# Hall_Sensorv0_1.net
KiCad netlist of a schematic drawn in EAGLE
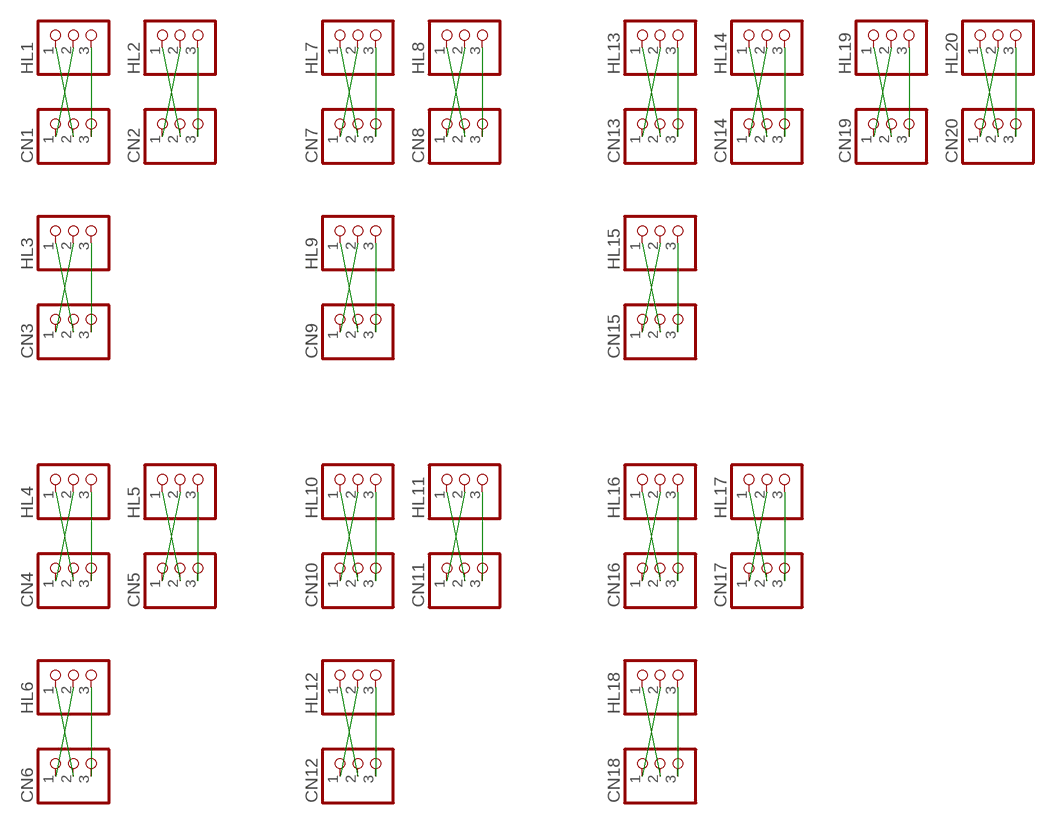
[diagram p0: schematic, sheet 1]

(export (version "E")
  (design (tool "Eeschema 10.0.6"))
  (components
    (comp (ref "CN1")
      (value "PINHD-1X3")
      (footprint "eagle-import:1X03")
      (libsource (lib "eagle-import") (part "PINHD-1X3"))
    )
    (comp (ref "CN2")
      (value "PINHD-1X3")
      (footprint "eagle-import:1X03")
      (libsource (lib "eagle-import") (part "PINHD-1X3"))
    )
    (comp (ref "CN3")
      (value "PINHD-1X3")
      (footprint "eagle-import:1X03")
      (libsource (lib "eagle-import") (part "PINHD-1X3"))
    )
    (comp (ref "CN4")
      (value "PINHD-1X3")
      (footprint "eagle-import:1X03")
      (libsource (lib "eagle-import") (part "PINHD-1X3"))
    )
    (comp (ref "CN5")
      (value "PINHD-1X3")
      (footprint "eagle-import:1X03")
      (libsource (lib "eagle-import") (part "PINHD-1X3"))
    )
    (comp (ref "CN6")
      (value "PINHD-1X3")
      (footprint "eagle-import:1X03")
      (libsource (lib "eagle-import") (part "PINHD-1X3"))
    )
    (comp (ref "CN7")
      (value "PINHD-1X3")
      (footprint "eagle-import:1X03")
      (libsource (lib "eagle-import") (part "PINHD-1X3"))
    )
    (comp (ref "CN8")
      (value "PINHD-1X3")
      (footprint "eagle-import:1X03")
      (libsource (lib "eagle-import") (part "PINHD-1X3"))
    )
    (comp (ref "CN9")
      (value "PINHD-1X3")
      (footprint "eagle-import:1X03")
      (libsource (lib "eagle-import") (part "PINHD-1X3"))
    )
    (comp (ref "CN10")
      (value "PINHD-1X3")
      (footprint "eagle-import:1X03")
      (libsource (lib "eagle-import") (part "PINHD-1X3"))
    )
    (comp (ref "CN11")
      (value "PINHD-1X3")
      (footprint "eagle-import:1X03")
      (libsource (lib "eagle-import") (part "PINHD-1X3"))
    )
    (comp (ref "CN12")
      (value "PINHD-1X3")
      (footprint "eagle-import:1X03")
      (libsource (lib "eagle-import") (part "PINHD-1X3"))
    )
    (comp (ref "CN13")
      (value "PINHD-1X3")
      (footprint "eagle-import:1X03")
      (libsource (lib "eagle-import") (part "PINHD-1X3"))
    )
    (comp (ref "CN14")
      (value "PINHD-1X3")
      (footprint "eagle-import:1X03")
      (libsource (lib "eagle-import") (part "PINHD-1X3"))
    )
    (comp (ref "CN15")
      (value "PINHD-1X3")
      (footprint "eagle-import:1X03")
      (libsource (lib "eagle-import") (part "PINHD-1X3"))
    )
    (comp (ref "CN16")
      (value "PINHD-1X3")
      (footprint "eagle-import:1X03")
      (libsource (lib "eagle-import") (part "PINHD-1X3"))
    )
    (comp (ref "CN17")
      (value "PINHD-1X3")
      (footprint "eagle-import:1X03")
      (libsource (lib "eagle-import") (part "PINHD-1X3"))
    )
    (comp (ref "CN18")
      (value "PINHD-1X3")
      (footprint "eagle-import:1X03")
      (libsource (lib "eagle-import") (part "PINHD-1X3"))
    )
    (comp (ref "CN19")
      (value "PINHD-1X3")
      (footprint "eagle-import:1X03")
      (libsource (lib "eagle-import") (part "PINHD-1X3"))
    )
    (comp (ref "CN20")
      (value "PINHD-1X3")
      (footprint "eagle-import:1X03")
      (libsource (lib "eagle-import") (part "PINHD-1X3"))
    )
    (comp (ref "HL1")
      (value "PINHD-1X3")
      (footprint "eagle-import:1X03")
      (libsource (lib "eagle-import") (part "PINHD-1X3"))
    )
    (comp (ref "HL2")
      (value "PINHD-1X3")
      (footprint "eagle-import:1X03")
      (libsource (lib "eagle-import") (part "PINHD-1X3"))
    )
    (comp (ref "HL3")
      (value "PINHD-1X3")
      (footprint "eagle-import:1X03")
      (libsource (lib "eagle-import") (part "PINHD-1X3"))
    )
    (comp (ref "HL4")
      (value "PINHD-1X3")
      (footprint "eagle-import:1X03")
      (libsource (lib "eagle-import") (part "PINHD-1X3"))
    )
    (comp (ref "HL5")
      (value "PINHD-1X3")
      (footprint "eagle-import:1X03")
      (libsource (lib "eagle-import") (part "PINHD-1X3"))
    )
    (comp (ref "HL6")
      (value "PINHD-1X3")
      (footprint "eagle-import:1X03")
      (libsource (lib "eagle-import") (part "PINHD-1X3"))
    )
    (comp (ref "HL7")
      (value "PINHD-1X3")
      (footprint "eagle-import:1X03")
      (libsource (lib "eagle-import") (part "PINHD-1X3"))
    )
    (comp (ref "HL8")
      (value "PINHD-1X3")
      (footprint "eagle-import:1X03")
      (libsource (lib "eagle-import") (part "PINHD-1X3"))
    )
    (comp (ref "HL9")
      (value "PINHD-1X3")
      (footprint "eagle-import:1X03")
      (libsource (lib "eagle-import") (part "PINHD-1X3"))
    )
    (comp (ref "HL10")
      (value "PINHD-1X3")
      (footprint "eagle-import:1X03")
      (libsource (lib "eagle-import") (part "PINHD-1X3"))
    )
    (comp (ref "HL11")
      (value "PINHD-1X3")
      (footprint "eagle-import:1X03")
      (libsource (lib "eagle-import") (part "PINHD-1X3"))
    )
    (comp (ref "HL12")
      (value "PINHD-1X3")
      (footprint "eagle-import:1X03")
      (libsource (lib "eagle-import") (part "PINHD-1X3"))
    )
    (comp (ref "HL13")
      (value "PINHD-1X3")
      (footprint "eagle-import:1X03")
      (libsource (lib "eagle-import") (part "PINHD-1X3"))
    )
    (comp (ref "HL14")
      (value "PINHD-1X3")
      (footprint "eagle-import:1X03")
      (libsource (lib "eagle-import") (part "PINHD-1X3"))
    )
    (comp (ref "HL15")
      (value "PINHD-1X3")
      (footprint "eagle-import:1X03")
      (libsource (lib "eagle-import") (part "PINHD-1X3"))
    )
    (comp (ref "HL16")
      (value "PINHD-1X3")
      (footprint "eagle-import:1X03")
      (libsource (lib "eagle-import") (part "PINHD-1X3"))
    )
    (comp (ref "HL17")
      (value "PINHD-1X3")
      (footprint "eagle-import:1X03")
      (libsource (lib "eagle-import") (part "PINHD-1X3"))
    )
    (comp (ref "HL18")
      (value "PINHD-1X3")
      (footprint "eagle-import:1X03")
      (libsource (lib "eagle-import") (part "PINHD-1X3"))
    )
    (comp (ref "HL19")
      (value "PINHD-1X3")
      (footprint "eagle-import:1X03")
      (libsource (lib "eagle-import") (part "PINHD-1X3"))
    )
    (comp (ref "HL20")
      (value "PINHD-1X3")
      (footprint "eagle-import:1X03")
      (libsource (lib "eagle-import") (part "PINHD-1X3"))
    )
  )
  (nets
    (net (code "1") (name "Net-(CN1-Pad1)") (class "Default")
      (node (ref "CN1") (pin "1") (pinfunction "1_1") (pintype "passive"))
      (node (ref "HL1") (pin "2") (pinfunction "2_2") (pintype "passive"))
    )
    (net (code "2") (name "Net-(CN1-Pad2)") (class "Default")
      (node (ref "CN1") (pin "2") (pinfunction "2_2") (pintype "passive"))
      (node (ref "HL1") (pin "1") (pinfunction "1_1") (pintype "passive"))
    )
    (net (code "3") (name "Net-(CN1-Pad3)") (class "Default")
      (node (ref "CN1") (pin "3") (pinfunction "3_3") (pintype "passive"))
      (node (ref "HL1") (pin "3") (pinfunction "3_3") (pintype "passive"))
    )
    (net (code "4") (name "Net-(CN2-Pad1)") (class "Default")
      (node (ref "CN2") (pin "1") (pinfunction "1_1") (pintype "passive"))
      (node (ref "HL2") (pin "2") (pinfunction "2_2") (pintype "passive"))
    )
    (net (code "5") (name "Net-(CN2-Pad2)") (class "Default")
      (node (ref "CN2") (pin "2") (pinfunction "2_2") (pintype "passive"))
      (node (ref "HL2") (pin "1") (pinfunction "1_1") (pintype "passive"))
    )
    (net (code "6") (name "Net-(CN2-Pad3)") (class "Default")
      (node (ref "CN2") (pin "3") (pinfunction "3_3") (pintype "passive"))
      (node (ref "HL2") (pin "3") (pinfunction "3_3") (pintype "passive"))
    )
    (net (code "7") (name "Net-(CN3-Pad1)") (class "Default")
      (node (ref "CN3") (pin "1") (pinfunction "1_1") (pintype "passive"))
      (node (ref "HL3") (pin "2") (pinfunction "2_2") (pintype "passive"))
    )
    (net (code "8") (name "Net-(CN3-Pad2)") (class "Default")
      (node (ref "CN3") (pin "2") (pinfunction "2_2") (pintype "passive"))
      (node (ref "HL3") (pin "1") (pinfunction "1_1") (pintype "passive"))
    )
    (net (code "9") (name "Net-(CN3-Pad3)") (class "Default")
      (node (ref "CN3") (pin "3") (pinfunction "3_3") (pintype "passive"))
      (node (ref "HL3") (pin "3") (pinfunction "3_3") (pintype "passive"))
    )
    (net (code "10") (name "Net-(CN4-Pad1)") (class "Default")
      (node (ref "CN4") (pin "1") (pinfunction "1_1") (pintype "passive"))
      (node (ref "HL4") (pin "2") (pinfunction "2_2") (pintype "passive"))
    )
    (net (code "11") (name "Net-(CN4-Pad2)") (class "Default")
      (node (ref "CN4") (pin "2") (pinfunction "2_2") (pintype "passive"))
      (node (ref "HL4") (pin "1") (pinfunction "1_1") (pintype "passive"))
    )
    (net (code "12") (name "Net-(CN4-Pad3)") (class "Default")
      (node (ref "CN4") (pin "3") (pinfunction "3_3") (pintype "passive"))
      (node (ref "HL4") (pin "3") (pinfunction "3_3") (pintype "passive"))
    )
    (net (code "13") (name "Net-(CN5-Pad1)") (class "Default")
      (node (ref "CN5") (pin "1") (pinfunction "1_1") (pintype "passive"))
      (node (ref "HL5") (pin "2") (pinfunction "2_2") (pintype "passive"))
    )
    (net (code "14") (name "Net-(CN5-Pad2)") (class "Default")
      (node (ref "CN5") (pin "2") (pinfunction "2_2") (pintype "passive"))
      (node (ref "HL5") (pin "1") (pinfunction "1_1") (pintype "passive"))
    )
    (net (code "15") (name "Net-(CN5-Pad3)") (class "Default")
      (node (ref "CN5") (pin "3") (pinfunction "3_3") (pintype "passive"))
      (node (ref "HL5") (pin "3") (pinfunction "3_3") (pintype "passive"))
    )
    (net (code "16") (name "Net-(CN6-Pad1)") (class "Default")
      (node (ref "CN6") (pin "1") (pinfunction "1_1") (pintype "passive"))
      (node (ref "HL6") (pin "2") (pinfunction "2_2") (pintype "passive"))
    )
    (net (code "17") (name "Net-(CN6-Pad2)") (class "Default")
      (node (ref "CN6") (pin "2") (pinfunction "2_2") (pintype "passive"))
      (node (ref "HL6") (pin "1") (pinfunction "1_1") (pintype "passive"))
    )
    (net (code "18") (name "Net-(CN6-Pad3)") (class "Default")
      (node (ref "CN6") (pin "3") (pinfunction "3_3") (pintype "passive"))
      (node (ref "HL6") (pin "3") (pinfunction "3_3") (pintype "passive"))
    )
    (net (code "19") (name "Net-(CN7-Pad1)") (class "Default")
      (node (ref "CN7") (pin "1") (pinfunction "1_1") (pintype "passive"))
      (node (ref "HL7") (pin "2") (pinfunction "2_2") (pintype "passive"))
    )
    (net (code "20") (name "Net-(CN7-Pad2)") (class "Default")
      (node (ref "CN7") (pin "2") (pinfunction "2_2") (pintype "passive"))
      (node (ref "HL7") (pin "1") (pinfunction "1_1") (pintype "passive"))
    )
    (net (code "21") (name "Net-(CN7-Pad3)") (class "Default")
      (node (ref "CN7") (pin "3") (pinfunction "3_3") (pintype "passive"))
      (node (ref "HL7") (pin "3") (pinfunction "3_3") (pintype "passive"))
    )
    (net (code "22") (name "Net-(CN8-Pad1)") (class "Default")
      (node (ref "CN8") (pin "1") (pinfunction "1_1") (pintype "passive"))
      (node (ref "HL8") (pin "2") (pinfunction "2_2") (pintype "passive"))
    )
    (net (code "23") (name "Net-(CN8-Pad2)") (class "Default")
      (node (ref "CN8") (pin "2") (pinfunction "2_2") (pintype "passive"))
      (node (ref "HL8") (pin "1") (pinfunction "1_1") (pintype "passive"))
    )
    (net (code "24") (name "Net-(CN8-Pad3)") (class "Default")
      (node (ref "CN8") (pin "3") (pinfunction "3_3") (pintype "passive"))
      (node (ref "HL8") (pin "3") (pinfunction "3_3") (pintype "passive"))
    )
    (net (code "25") (name "Net-(CN9-Pad1)") (class "Default")
      (node (ref "CN9") (pin "1") (pinfunction "1_1") (pintype "passive"))
      (node (ref "HL9") (pin "2") (pinfunction "2_2") (pintype "passive"))
    )
    (net (code "26") (name "Net-(CN9-Pad2)") (class "Default")
      (node (ref "CN9") (pin "2") (pinfunction "2_2") (pintype "passive"))
      (node (ref "HL9") (pin "1") (pinfunction "1_1") (pintype "passive"))
    )
    (net (code "27") (name "Net-(CN9-Pad3)") (class "Default")
      (node (ref "CN9") (pin "3") (pinfunction "3_3") (pintype "passive"))
      (node (ref "HL9") (pin "3") (pinfunction "3_3") (pintype "passive"))
    )
    (net (code "28") (name "Net-(CN10-Pad1)") (class "Default")
      (node (ref "CN10") (pin "1") (pinfunction "1_1") (pintype "passive"))
      (node (ref "HL10") (pin "2") (pinfunction "2_2") (pintype "passive"))
    )
    (net (code "29") (name "Net-(CN10-Pad2)") (class "Default")
      (node (ref "CN10") (pin "2") (pinfunction "2_2") (pintype "passive"))
      (node (ref "HL10") (pin "1") (pinfunction "1_1") (pintype "passive"))
    )
    (net (code "30") (name "Net-(CN10-Pad3)") (class "Default")
      (node (ref "CN10") (pin "3") (pinfunction "3_3") (pintype "passive"))
      (node (ref "HL10") (pin "3") (pinfunction "3_3") (pintype "passive"))
    )
    (net (code "31") (name "Net-(CN11-Pad1)") (class "Default")
      (node (ref "CN11") (pin "1") (pinfunction "1_1") (pintype "passive"))
      (node (ref "HL11") (pin "2") (pinfunction "2_2") (pintype "passive"))
    )
    (net (code "32") (name "Net-(CN11-Pad2)") (class "Default")
      (node (ref "CN11") (pin "2") (pinfunction "2_2") (pintype "passive"))
      (node (ref "HL11") (pin "1") (pinfunction "1_1") (pintype "passive"))
    )
    (net (code "33") (name "Net-(CN11-Pad3)") (class "Default")
      (node (ref "CN11") (pin "3") (pinfunction "3_3") (pintype "passive"))
      (node (ref "HL11") (pin "3") (pinfunction "3_3") (pintype "passive"))
    )
    (net (code "34") (name "Net-(CN12-Pad1)") (class "Default")
      (node (ref "CN12") (pin "1") (pinfunction "1_1") (pintype "passive"))
      (node (ref "HL12") (pin "2") (pinfunction "2_2") (pintype "passive"))
    )
    (net (code "35") (name "Net-(CN12-Pad2)") (class "Default")
      (node (ref "CN12") (pin "2") (pinfunction "2_2") (pintype "passive"))
      (node (ref "HL12") (pin "1") (pinfunction "1_1") (pintype "passive"))
    )
    (net (code "36") (name "Net-(CN12-Pad3)") (class "Default")
      (node (ref "CN12") (pin "3") (pinfunction "3_3") (pintype "passive"))
      (node (ref "HL12") (pin "3") (pinfunction "3_3") (pintype "passive"))
    )
    (net (code "37") (name "Net-(CN13-Pad1)") (class "Default")
      (node (ref "CN13") (pin "1") (pinfunction "1_1") (pintype "passive"))
      (node (ref "HL13") (pin "2") (pinfunction "2_2") (pintype "passive"))
    )
    (net (code "38") (name "Net-(CN13-Pad2)") (class "Default")
      (node (ref "CN13") (pin "2") (pinfunction "2_2") (pintype "passive"))
      (node (ref "HL13") (pin "1") (pinfunction "1_1") (pintype "passive"))
    )
    (net (code "39") (name "Net-(CN13-Pad3)") (class "Default")
      (node (ref "CN13") (pin "3") (pinfunction "3_3") (pintype "passive"))
      (node (ref "HL13") (pin "3") (pinfunction "3_3") (pintype "passive"))
    )
    (net (code "40") (name "Net-(CN14-Pad1)") (class "Default")
      (node (ref "CN14") (pin "1") (pinfunction "1_1") (pintype "passive"))
      (node (ref "HL14") (pin "2") (pinfunction "2_2") (pintype "passive"))
    )
    (net (code "41") (name "Net-(CN14-Pad2)") (class "Default")
      (node (ref "CN14") (pin "2") (pinfunction "2_2") (pintype "passive"))
      (node (ref "HL14") (pin "1") (pinfunction "1_1") (pintype "passive"))
    )
    (net (code "42") (name "Net-(CN14-Pad3)") (class "Default")
      (node (ref "CN14") (pin "3") (pinfunction "3_3") (pintype "passive"))
      (node (ref "HL14") (pin "3") (pinfunction "3_3") (pintype "passive"))
    )
    (net (code "43") (name "Net-(CN15-Pad1)") (class "Default")
      (node (ref "CN15") (pin "1") (pinfunction "1_1") (pintype "passive"))
      (node (ref "HL15") (pin "2") (pinfunction "2_2") (pintype "passive"))
    )
    (net (code "44") (name "Net-(CN15-Pad2)") (class "Default")
      (node (ref "CN15") (pin "2") (pinfunction "2_2") (pintype "passive"))
      (node (ref "HL15") (pin "1") (pinfunction "1_1") (pintype "passive"))
    )
    (net (code "45") (name "Net-(CN15-Pad3)") (class "Default")
      (node (ref "CN15") (pin "3") (pinfunction "3_3") (pintype "passive"))
      (node (ref "HL15") (pin "3") (pinfunction "3_3") (pintype "passive"))
    )
    (net (code "46") (name "Net-(CN16-Pad1)") (class "Default")
      (node (ref "CN16") (pin "1") (pinfunction "1_1") (pintype "passive"))
      (node (ref "HL16") (pin "2") (pinfunction "2_2") (pintype "passive"))
    )
    (net (code "47") (name "Net-(CN16-Pad2)") (class "Default")
      (node (ref "CN16") (pin "2") (pinfunction "2_2") (pintype "passive"))
      (node (ref "HL16") (pin "1") (pinfunction "1_1") (pintype "passive"))
    )
    (net (code "48") (name "Net-(CN16-Pad3)") (class "Default")
      (node (ref "CN16") (pin "3") (pinfunction "3_3") (pintype "passive"))
      (node (ref "HL16") (pin "3") (pinfunction "3_3") (pintype "passive"))
    )
    (net (code "49") (name "Net-(CN17-Pad1)") (class "Default")
      (node (ref "CN17") (pin "1") (pinfunction "1_1") (pintype "passive"))
      (node (ref "HL17") (pin "2") (pinfunction "2_2") (pintype "passive"))
    )
    (net (code "50") (name "Net-(CN17-Pad2)") (class "Default")
      (node (ref "CN17") (pin "2") (pinfunction "2_2") (pintype "passive"))
      (node (ref "HL17") (pin "1") (pinfunction "1_1") (pintype "passive"))
    )
    (net (code "51") (name "Net-(CN17-Pad3)") (class "Default")
      (node (ref "CN17") (pin "3") (pinfunction "3_3") (pintype "passive"))
      (node (ref "HL17") (pin "3") (pinfunction "3_3") (pintype "passive"))
    )
    (net (code "52") (name "Net-(CN18-Pad1)") (class "Default")
      (node (ref "CN18") (pin "1") (pinfunction "1_1") (pintype "passive"))
      (node (ref "HL18") (pin "2") (pinfunction "2_2") (pintype "passive"))
    )
    (net (code "53") (name "Net-(CN18-Pad2)") (class "Default")
      (node (ref "CN18") (pin "2") (pinfunction "2_2") (pintype "passive"))
      (node (ref "HL18") (pin "1") (pinfunction "1_1") (pintype "passive"))
    )
    (net (code "54") (name "Net-(CN18-Pad3)") (class "Default")
      (node (ref "CN18") (pin "3") (pinfunction "3_3") (pintype "passive"))
      (node (ref "HL18") (pin "3") (pinfunction "3_3") (pintype "passive"))
    )
    (net (code "55") (name "Net-(CN19-Pad1)") (class "Default")
      (node (ref "CN19") (pin "1") (pinfunction "1_1") (pintype "passive"))
      (node (ref "HL19") (pin "2") (pinfunction "2_2") (pintype "passive"))
    )
    (net (code "56") (name "Net-(CN19-Pad2)") (class "Default")
      (node (ref "CN19") (pin "2") (pinfunction "2_2") (pintype "passive"))
      (node (ref "HL19") (pin "1") (pinfunction "1_1") (pintype "passive"))
    )
    (net (code "57") (name "Net-(CN19-Pad3)") (class "Default")
      (node (ref "CN19") (pin "3") (pinfunction "3_3") (pintype "passive"))
      (node (ref "HL19") (pin "3") (pinfunction "3_3") (pintype "passive"))
    )
    (net (code "58") (name "Net-(CN20-Pad1)") (class "Default")
      (node (ref "CN20") (pin "1") (pinfunction "1_1") (pintype "passive"))
      (node (ref "HL20") (pin "2") (pinfunction "2_2") (pintype "passive"))
    )
    (net (code "59") (name "Net-(CN20-Pad2)") (class "Default")
      (node (ref "CN20") (pin "2") (pinfunction "2_2") (pintype "passive"))
      (node (ref "HL20") (pin "1") (pinfunction "1_1") (pintype "passive"))
    )
    (net (code "60") (name "Net-(CN20-Pad3)") (class "Default")
      (node (ref "CN20") (pin "3") (pinfunction "3_3") (pintype "passive"))
      (node (ref "HL20") (pin "3") (pinfunction "3_3") (pintype "passive"))
    )
  )
)
